# tigerV3s0-2.net
KiCad netlist of a schematic drawn in EAGLE
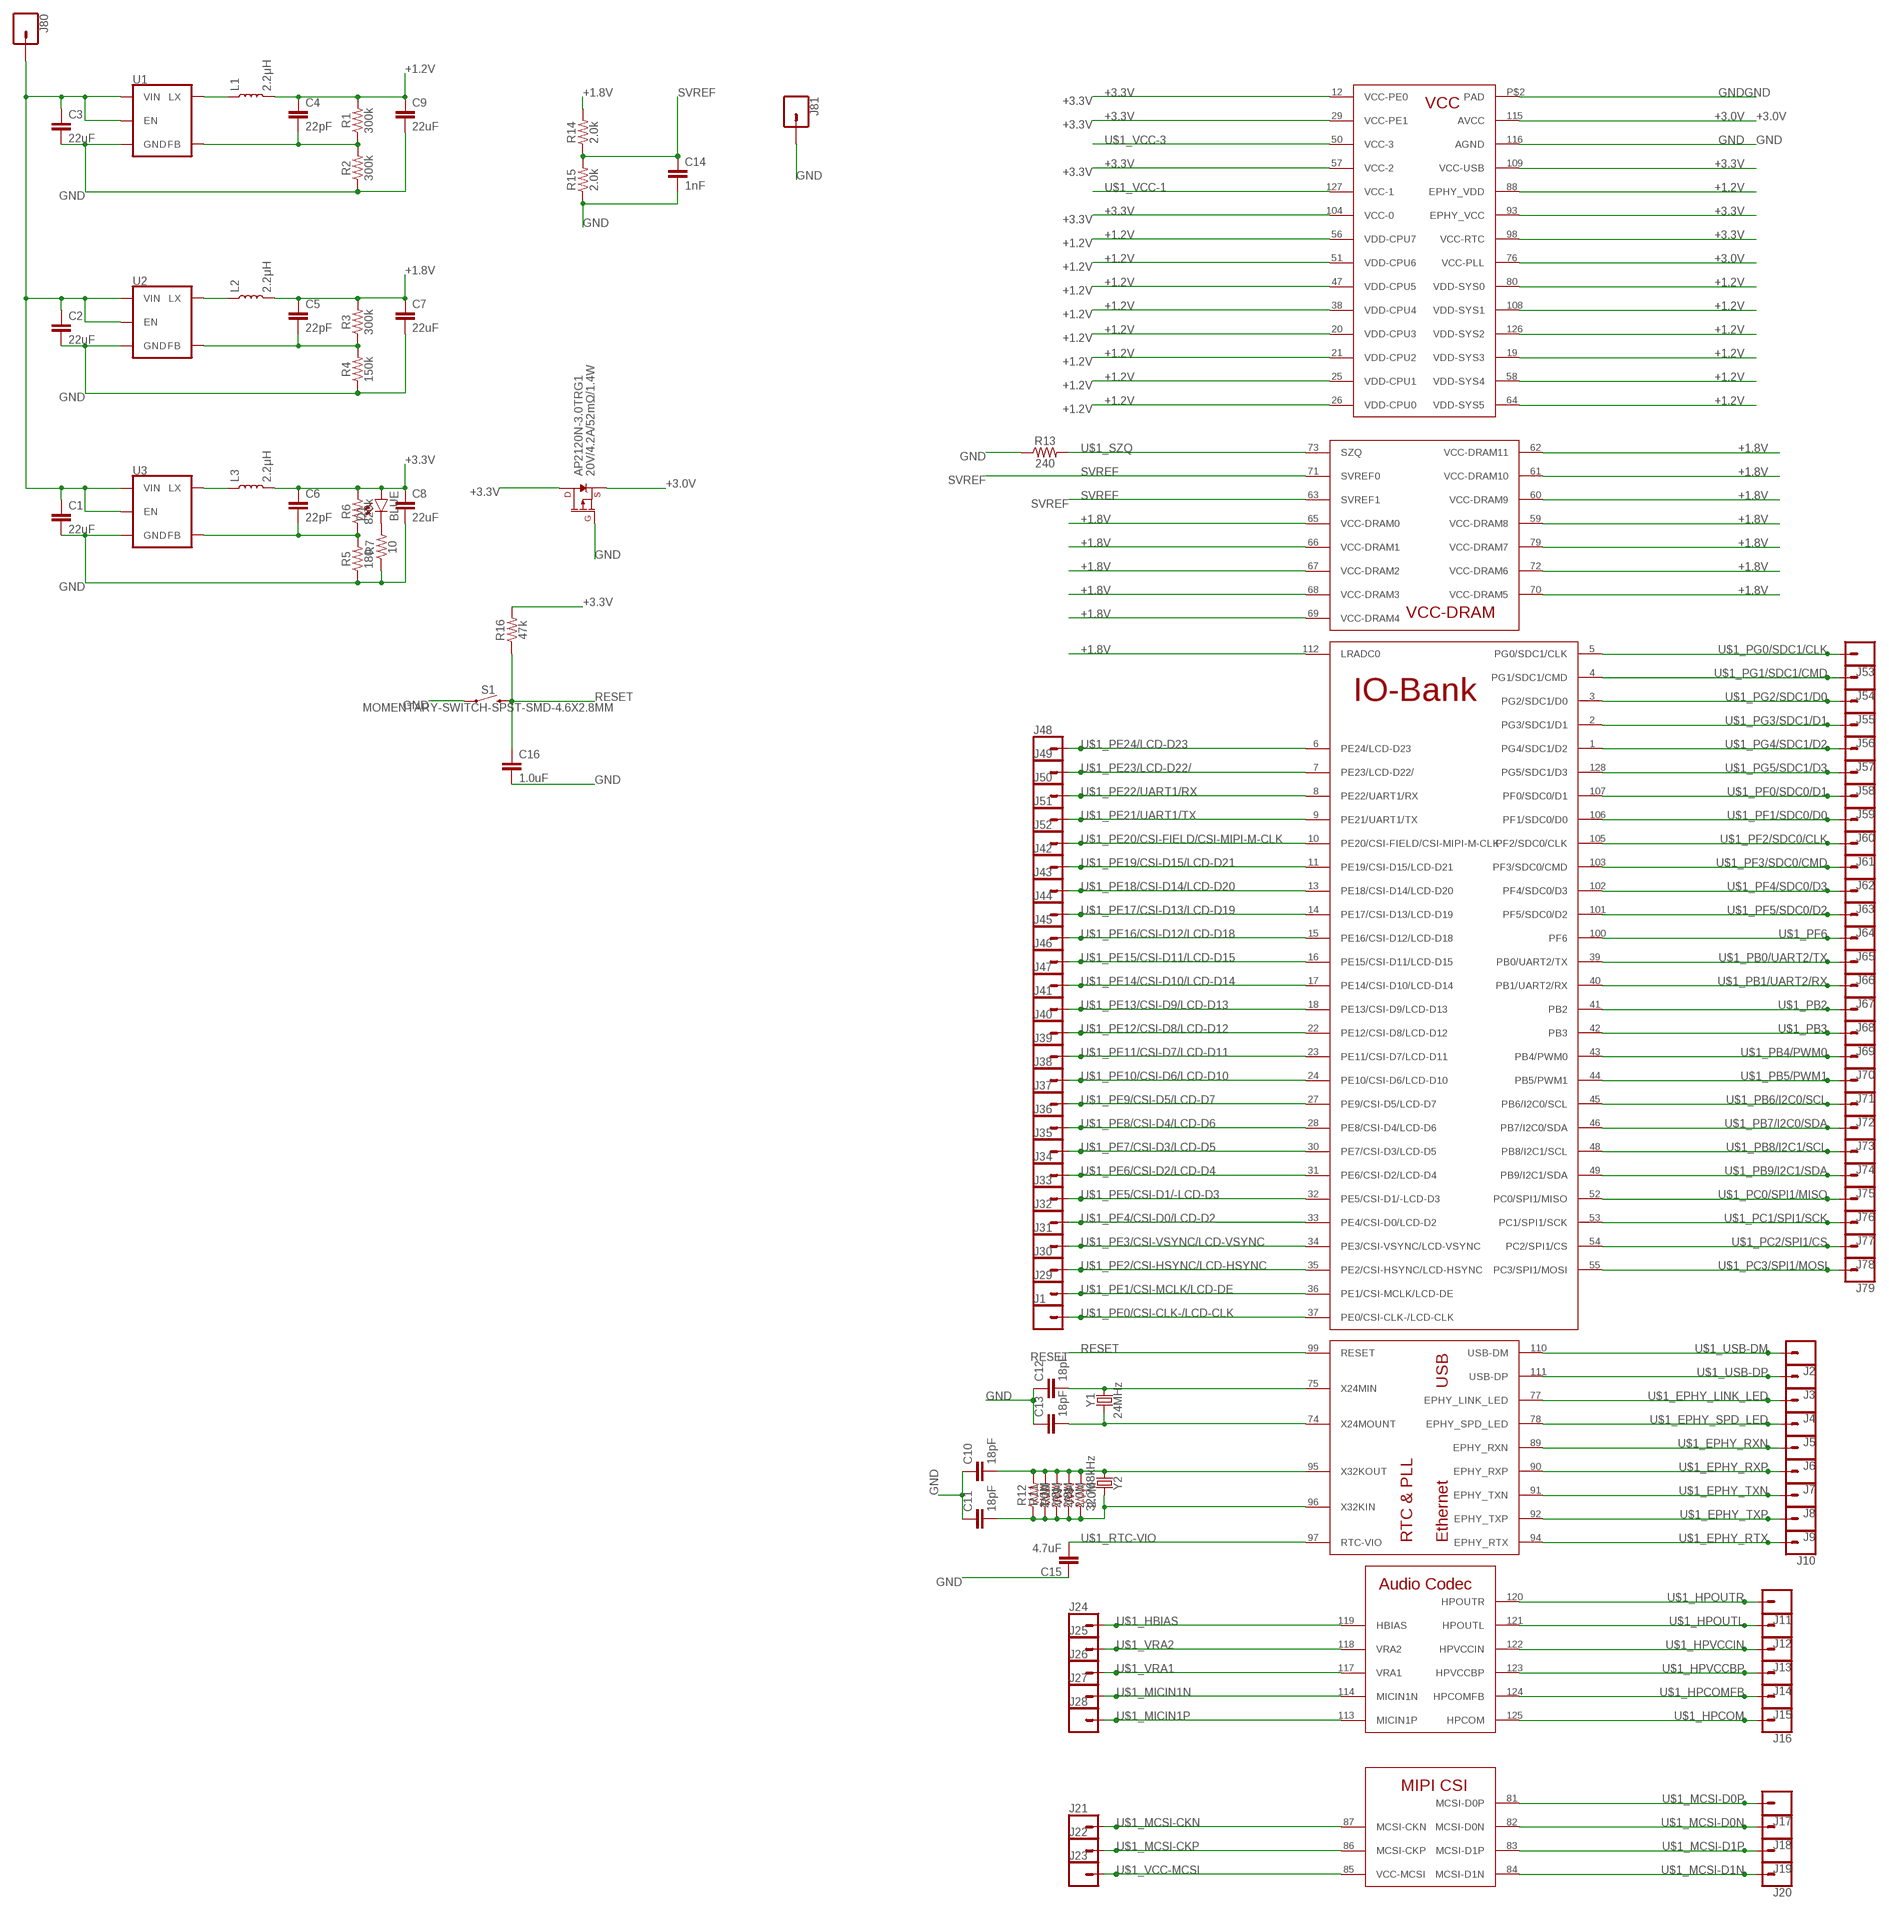
[diagram p0: schematic, sheet 1]

(export (version "E")
  (design (tool "Eeschema 10.0.6"))
  (components
    (comp (ref "AP2120N-3.0TRG1")
      (value "20V/4.2A/52mΩ/1.4W")
      (footprint "eagle-import:SOT23-3")
      (libsource (lib "eagle-import") (part "MOSFET_PCH-DMG2305UX-7"))
    )
    (comp (ref "C1")
      (value "22uF")
      (footprint "eagle-import:0805")
      (libsource (lib "eagle-import") (part "22UF-0805-6.3V-20%"))
    )
    (comp (ref "C2")
      (value "22uF")
      (footprint "eagle-import:0805")
      (libsource (lib "eagle-import") (part "22UF-0805-6.3V-20%"))
    )
    (comp (ref "C3")
      (value "22uF")
      (footprint "eagle-import:0805")
      (libsource (lib "eagle-import") (part "22UF-0805-6.3V-20%"))
    )
    (comp (ref "C4")
      (value "22pF")
      (footprint "eagle-import:0603")
      (libsource (lib "eagle-import") (part "22PF-0603-50V-5%"))
    )
    (comp (ref "C5")
      (value "22pF")
      (footprint "eagle-import:0603")
      (libsource (lib "eagle-import") (part "22PF-0603-50V-5%"))
    )
    (comp (ref "C6")
      (value "22pF")
      (footprint "eagle-import:0603")
      (libsource (lib "eagle-import") (part "22PF-0603-50V-5%"))
    )
    (comp (ref "C7")
      (value "22uF")
      (footprint "eagle-import:0805")
      (libsource (lib "eagle-import") (part "22UF-0805-6.3V-20%"))
    )
    (comp (ref "C8")
      (value "22uF")
      (footprint "eagle-import:0805")
      (libsource (lib "eagle-import") (part "22UF-0805-6.3V-20%"))
    )
    (comp (ref "C9")
      (value "22uF")
      (footprint "eagle-import:0805")
      (libsource (lib "eagle-import") (part "22UF-0805-6.3V-20%"))
    )
    (comp (ref "C10")
      (value "18pF")
      (footprint "eagle-import:0603")
      (libsource (lib "eagle-import") (part "18PF-0603-50V-5%"))
    )
    (comp (ref "C11")
      (value "18pF")
      (footprint "eagle-import:0603")
      (libsource (lib "eagle-import") (part "18PF-0603-50V-5%"))
    )
    (comp (ref "C12")
      (value "18pF")
      (footprint "eagle-import:0603")
      (libsource (lib "eagle-import") (part "18PF-0603-50V-5%"))
    )
    (comp (ref "C13")
      (value "18pF")
      (footprint "eagle-import:0603")
      (libsource (lib "eagle-import") (part "18PF-0603-50V-5%"))
    )
    (comp (ref "C14")
      (value "1nF")
      (footprint "eagle-import:0603")
      (libsource (lib "eagle-import") (part "1.0NF/1000PF-0603-50V-10%"))
    )
    (comp (ref "C15")
      (value "4.7uF")
      (footprint "eagle-import:0603")
      (libsource (lib "eagle-import") (part "4.7UF-0603-6.3V-(10%)"))
    )
    (comp (ref "C16")
      (value "1.0uF")
      (footprint "eagle-import:0603")
      (libsource (lib "eagle-import") (part "1.0UF-0603-16V-10%"))
    )
    (comp (ref "D1")
      (value "BLUE")
      (footprint "eagle-import:LED-0603")
      (libsource (lib "eagle-import") (part "LED-BLUE0603"))
    )
    (comp (ref "J1")
      (value "CONN_01")
      (footprint "eagle-import:1X01")
      (libsource (lib "eagle-import") (part "CONN_01"))
    )
    (comp (ref "J2")
      (value "CONN_01")
      (footprint "eagle-import:1X01")
      (libsource (lib "eagle-import") (part "CONN_01"))
    )
    (comp (ref "J3")
      (value "CONN_01")
      (footprint "eagle-import:1X01")
      (libsource (lib "eagle-import") (part "CONN_01"))
    )
    (comp (ref "J4")
      (value "CONN_01")
      (footprint "eagle-import:1X01")
      (libsource (lib "eagle-import") (part "CONN_01"))
    )
    (comp (ref "J5")
      (value "CONN_01")
      (footprint "eagle-import:1X01")
      (libsource (lib "eagle-import") (part "CONN_01"))
    )
    (comp (ref "J6")
      (value "CONN_01")
      (footprint "eagle-import:1X01")
      (libsource (lib "eagle-import") (part "CONN_01"))
    )
    (comp (ref "J7")
      (value "CONN_01")
      (footprint "eagle-import:1X01")
      (libsource (lib "eagle-import") (part "CONN_01"))
    )
    (comp (ref "J8")
      (value "CONN_01")
      (footprint "eagle-import:1X01")
      (libsource (lib "eagle-import") (part "CONN_01"))
    )
    (comp (ref "J9")
      (value "CONN_01")
      (footprint "eagle-import:1X01")
      (libsource (lib "eagle-import") (part "CONN_01"))
    )
    (comp (ref "J10")
      (value "CONN_01")
      (footprint "eagle-import:1X01")
      (libsource (lib "eagle-import") (part "CONN_01"))
    )
    (comp (ref "J11")
      (value "CONN_01")
      (footprint "eagle-import:1X01")
      (libsource (lib "eagle-import") (part "CONN_01"))
    )
    (comp (ref "J12")
      (value "CONN_01")
      (footprint "eagle-import:1X01")
      (libsource (lib "eagle-import") (part "CONN_01"))
    )
    (comp (ref "J13")
      (value "CONN_01")
      (footprint "eagle-import:1X01")
      (libsource (lib "eagle-import") (part "CONN_01"))
    )
    (comp (ref "J14")
      (value "CONN_01")
      (footprint "eagle-import:1X01")
      (libsource (lib "eagle-import") (part "CONN_01"))
    )
    (comp (ref "J15")
      (value "CONN_01")
      (footprint "eagle-import:1X01")
      (libsource (lib "eagle-import") (part "CONN_01"))
    )
    (comp (ref "J16")
      (value "CONN_01")
      (footprint "eagle-import:1X01")
      (libsource (lib "eagle-import") (part "CONN_01"))
    )
    (comp (ref "J17")
      (value "CONN_01")
      (footprint "eagle-import:1X01")
      (libsource (lib "eagle-import") (part "CONN_01"))
    )
    (comp (ref "J18")
      (value "CONN_01")
      (footprint "eagle-import:1X01")
      (libsource (lib "eagle-import") (part "CONN_01"))
    )
    (comp (ref "J19")
      (value "CONN_01")
      (footprint "eagle-import:1X01")
      (libsource (lib "eagle-import") (part "CONN_01"))
    )
    (comp (ref "J20")
      (value "CONN_01")
      (footprint "eagle-import:1X01")
      (libsource (lib "eagle-import") (part "CONN_01"))
    )
    (comp (ref "J21")
      (value "CONN_01")
      (footprint "eagle-import:1X01")
      (libsource (lib "eagle-import") (part "CONN_01"))
    )
    (comp (ref "J22")
      (value "CONN_01")
      (footprint "eagle-import:1X01")
      (libsource (lib "eagle-import") (part "CONN_01"))
    )
    (comp (ref "J23")
      (value "CONN_01")
      (footprint "eagle-import:1X01")
      (libsource (lib "eagle-import") (part "CONN_01"))
    )
    (comp (ref "J24")
      (value "CONN_01")
      (footprint "eagle-import:1X01")
      (libsource (lib "eagle-import") (part "CONN_01"))
    )
    (comp (ref "J25")
      (value "CONN_01")
      (footprint "eagle-import:1X01")
      (libsource (lib "eagle-import") (part "CONN_01"))
    )
    (comp (ref "J26")
      (value "CONN_01")
      (footprint "eagle-import:1X01")
      (libsource (lib "eagle-import") (part "CONN_01"))
    )
    (comp (ref "J27")
      (value "CONN_01")
      (footprint "eagle-import:1X01")
      (libsource (lib "eagle-import") (part "CONN_01"))
    )
    (comp (ref "J28")
      (value "CONN_01")
      (footprint "eagle-import:1X01")
      (libsource (lib "eagle-import") (part "CONN_01"))
    )
    (comp (ref "J29")
      (value "CONN_01")
      (footprint "eagle-import:1X01")
      (libsource (lib "eagle-import") (part "CONN_01"))
    )
    (comp (ref "J30")
      (value "CONN_01")
      (footprint "eagle-import:1X01")
      (libsource (lib "eagle-import") (part "CONN_01"))
    )
    (comp (ref "J31")
      (value "CONN_01")
      (footprint "eagle-import:1X01")
      (libsource (lib "eagle-import") (part "CONN_01"))
    )
    (comp (ref "J32")
      (value "CONN_01")
      (footprint "eagle-import:1X01")
      (libsource (lib "eagle-import") (part "CONN_01"))
    )
    (comp (ref "J33")
      (value "CONN_01")
      (footprint "eagle-import:1X01")
      (libsource (lib "eagle-import") (part "CONN_01"))
    )
    (comp (ref "J34")
      (value "CONN_01")
      (footprint "eagle-import:1X01")
      (libsource (lib "eagle-import") (part "CONN_01"))
    )
    (comp (ref "J35")
      (value "CONN_01")
      (footprint "eagle-import:1X01")
      (libsource (lib "eagle-import") (part "CONN_01"))
    )
    (comp (ref "J36")
      (value "CONN_01")
      (footprint "eagle-import:1X01")
      (libsource (lib "eagle-import") (part "CONN_01"))
    )
    (comp (ref "J37")
      (value "CONN_01")
      (footprint "eagle-import:1X01")
      (libsource (lib "eagle-import") (part "CONN_01"))
    )
    (comp (ref "J38")
      (value "CONN_01")
      (footprint "eagle-import:1X01")
      (libsource (lib "eagle-import") (part "CONN_01"))
    )
    (comp (ref "J39")
      (value "CONN_01")
      (footprint "eagle-import:1X01")
      (libsource (lib "eagle-import") (part "CONN_01"))
    )
    (comp (ref "J40")
      (value "CONN_01")
      (footprint "eagle-import:1X01")
      (libsource (lib "eagle-import") (part "CONN_01"))
    )
    (comp (ref "J41")
      (value "CONN_01")
      (footprint "eagle-import:1X01")
      (libsource (lib "eagle-import") (part "CONN_01"))
    )
    (comp (ref "J42")
      (value "CONN_01")
      (footprint "eagle-import:1X01")
      (libsource (lib "eagle-import") (part "CONN_01"))
    )
    (comp (ref "J43")
      (value "CONN_01")
      (footprint "eagle-import:1X01")
      (libsource (lib "eagle-import") (part "CONN_01"))
    )
    (comp (ref "J44")
      (value "CONN_01")
      (footprint "eagle-import:1X01")
      (libsource (lib "eagle-import") (part "CONN_01"))
    )
    (comp (ref "J45")
      (value "CONN_01")
      (footprint "eagle-import:1X01")
      (libsource (lib "eagle-import") (part "CONN_01"))
    )
    (comp (ref "J46")
      (value "CONN_01")
      (footprint "eagle-import:1X01")
      (libsource (lib "eagle-import") (part "CONN_01"))
    )
    (comp (ref "J47")
      (value "CONN_01")
      (footprint "eagle-import:1X01")
      (libsource (lib "eagle-import") (part "CONN_01"))
    )
    (comp (ref "J48")
      (value "CONN_01")
      (footprint "eagle-import:1X01")
      (libsource (lib "eagle-import") (part "CONN_01"))
    )
    (comp (ref "J49")
      (value "CONN_01")
      (footprint "eagle-import:1X01")
      (libsource (lib "eagle-import") (part "CONN_01"))
    )
    (comp (ref "J50")
      (value "CONN_01")
      (footprint "eagle-import:1X01")
      (libsource (lib "eagle-import") (part "CONN_01"))
    )
    (comp (ref "J51")
      (value "CONN_01")
      (footprint "eagle-import:1X01")
      (libsource (lib "eagle-import") (part "CONN_01"))
    )
    (comp (ref "J52")
      (value "CONN_01")
      (footprint "eagle-import:1X01")
      (libsource (lib "eagle-import") (part "CONN_01"))
    )
    (comp (ref "J53")
      (value "CONN_01")
      (footprint "eagle-import:1X01")
      (libsource (lib "eagle-import") (part "CONN_01"))
    )
    (comp (ref "J54")
      (value "CONN_01")
      (footprint "eagle-import:1X01")
      (libsource (lib "eagle-import") (part "CONN_01"))
    )
    (comp (ref "J55")
      (value "CONN_01")
      (footprint "eagle-import:1X01")
      (libsource (lib "eagle-import") (part "CONN_01"))
    )
    (comp (ref "J56")
      (value "CONN_01")
      (footprint "eagle-import:1X01")
      (libsource (lib "eagle-import") (part "CONN_01"))
    )
    (comp (ref "J57")
      (value "CONN_01")
      (footprint "eagle-import:1X01")
      (libsource (lib "eagle-import") (part "CONN_01"))
    )
    (comp (ref "J58")
      (value "CONN_01")
      (footprint "eagle-import:1X01")
      (libsource (lib "eagle-import") (part "CONN_01"))
    )
    (comp (ref "J59")
      (value "CONN_01")
      (footprint "eagle-import:1X01")
      (libsource (lib "eagle-import") (part "CONN_01"))
    )
    (comp (ref "J60")
      (value "CONN_01")
      (footprint "eagle-import:1X01")
      (libsource (lib "eagle-import") (part "CONN_01"))
    )
    (comp (ref "J61")
      (value "CONN_01")
      (footprint "eagle-import:1X01")
      (libsource (lib "eagle-import") (part "CONN_01"))
    )
    (comp (ref "J62")
      (value "CONN_01")
      (footprint "eagle-import:1X01")
      (libsource (lib "eagle-import") (part "CONN_01"))
    )
    (comp (ref "J63")
      (value "CONN_01")
      (footprint "eagle-import:1X01")
      (libsource (lib "eagle-import") (part "CONN_01"))
    )
    (comp (ref "J64")
      (value "CONN_01")
      (footprint "eagle-import:1X01")
      (libsource (lib "eagle-import") (part "CONN_01"))
    )
    (comp (ref "J65")
      (value "CONN_01")
      (footprint "eagle-import:1X01")
      (libsource (lib "eagle-import") (part "CONN_01"))
    )
    (comp (ref "J66")
      (value "CONN_01")
      (footprint "eagle-import:1X01")
      (libsource (lib "eagle-import") (part "CONN_01"))
    )
    (comp (ref "J67")
      (value "CONN_01")
      (footprint "eagle-import:1X01")
      (libsource (lib "eagle-import") (part "CONN_01"))
    )
    (comp (ref "J68")
      (value "CONN_01")
      (footprint "eagle-import:1X01")
      (libsource (lib "eagle-import") (part "CONN_01"))
    )
    (comp (ref "J69")
      (value "CONN_01")
      (footprint "eagle-import:1X01")
      (libsource (lib "eagle-import") (part "CONN_01"))
    )
    (comp (ref "J70")
      (value "CONN_01")
      (footprint "eagle-import:1X01")
      (libsource (lib "eagle-import") (part "CONN_01"))
    )
    (comp (ref "J71")
      (value "CONN_01")
      (footprint "eagle-import:1X01")
      (libsource (lib "eagle-import") (part "CONN_01"))
    )
    (comp (ref "J72")
      (value "CONN_01")
      (footprint "eagle-import:1X01")
      (libsource (lib "eagle-import") (part "CONN_01"))
    )
    (comp (ref "J73")
      (value "CONN_01")
      (footprint "eagle-import:1X01")
      (libsource (lib "eagle-import") (part "CONN_01"))
    )
    (comp (ref "J74")
      (value "CONN_01")
      (footprint "eagle-import:1X01")
      (libsource (lib "eagle-import") (part "CONN_01"))
    )
    (comp (ref "J75")
      (value "CONN_01")
      (footprint "eagle-import:1X01")
      (libsource (lib "eagle-import") (part "CONN_01"))
    )
    (comp (ref "J76")
      (value "CONN_01")
      (footprint "eagle-import:1X01")
      (libsource (lib "eagle-import") (part "CONN_01"))
    )
    (comp (ref "J77")
      (value "CONN_01")
      (footprint "eagle-import:1X01")
      (libsource (lib "eagle-import") (part "CONN_01"))
    )
    (comp (ref "J78")
      (value "CONN_01")
      (footprint "eagle-import:1X01")
      (libsource (lib "eagle-import") (part "CONN_01"))
    )
    (comp (ref "J79")
      (value "CONN_01")
      (footprint "eagle-import:1X01")
      (libsource (lib "eagle-import") (part "CONN_01"))
    )
    (comp (ref "J80")
      (value "CONN_01")
      (footprint "eagle-import:1X01")
      (libsource (lib "eagle-import") (part "CONN_01"))
    )
    (comp (ref "J81")
      (value "CONN_01")
      (footprint "eagle-import:1X01")
      (libsource (lib "eagle-import") (part "CONN_01"))
    )
    (comp (ref "L1")
      (value "2.2μH")
      (footprint "eagle-import:0805-WIDE")
      (libsource (lib "eagle-import") (part "2.2μH-0805_WIDE-2.2μH-1.7A-0.14OHM"))
    )
    (comp (ref "L2")
      (value "2.2μH")
      (footprint "eagle-import:0805-WIDE")
      (libsource (lib "eagle-import") (part "2.2μH-0805_WIDE-2.2μH-1.7A-0.14OHM"))
    )
    (comp (ref "L3")
      (value "2.2μH")
      (footprint "eagle-import:0805-WIDE")
      (libsource (lib "eagle-import") (part "2.2μH-0805_WIDE-2.2μH-1.7A-0.14OHM"))
    )
    (comp (ref "R1")
      (value "300k")
      (footprint "eagle-import:0603")
      (libsource (lib "eagle-import") (part "300KOHM-0603-1/10W-1%"))
    )
    (comp (ref "R2")
      (value "300k")
      (footprint "eagle-import:0603")
      (libsource (lib "eagle-import") (part "300KOHM-0603-1/10W-1%"))
    )
    (comp (ref "R3")
      (value "300k")
      (footprint "eagle-import:0603")
      (libsource (lib "eagle-import") (part "300KOHM-0603-1/10W-1%"))
    )
    (comp (ref "R4")
      (value "150k")
      (footprint "eagle-import:0603")
      (libsource (lib "eagle-import") (part "150KOHM-0603-1/10W-1%"))
    )
    (comp (ref "R5")
      (value "180")
      (footprint "eagle-import:0603")
      (libsource (lib "eagle-import") (part "180OHM-0603-1/10W-1%"))
    )
    (comp (ref "R6")
      (value "820k")
      (footprint "eagle-import:0603")
      (libsource (lib "eagle-import") (part "820KOHM-0603-1/10W-1%"))
    )
    (comp (ref "R7")
      (value "10")
      (footprint "eagle-import:0603")
      (libsource (lib "eagle-import") (part "10OHM-0603-1/10W-1%"))
    )
    (comp (ref "R8")
      (value "2.0M")
      (footprint "eagle-import:0603")
      (libsource (lib "eagle-import") (part "2MOHMS-0603-1/10W-1%"))
    )
    (comp (ref "R9")
      (value "2.0M")
      (footprint "eagle-import:0603")
      (libsource (lib "eagle-import") (part "2MOHMS-0603-1/10W-1%"))
    )
    (comp (ref "R10")
      (value "2.0M")
      (footprint "eagle-import:0603")
      (libsource (lib "eagle-import") (part "2MOHMS-0603-1/10W-1%"))
    )
    (comp (ref "R11")
      (value "2.0M")
      (footprint "eagle-import:0603")
      (libsource (lib "eagle-import") (part "2MOHMS-0603-1/10W-1%"))
    )
    (comp (ref "R12")
      (value "2.0M")
      (footprint "eagle-import:0603")
      (libsource (lib "eagle-import") (part "2MOHMS-0603-1/10W-1%"))
    )
    (comp (ref "R13")
      (value "240")
      (footprint "eagle-import:0603")
      (libsource (lib "eagle-import") (part "240OHM-0603-1/10W-1%"))
    )
    (comp (ref "R14")
      (value "2.0k")
      (footprint "eagle-import:0603")
      (libsource (lib "eagle-import") (part "2.0KOHM-0603-1/10W-5%"))
    )
    (comp (ref "R15")
      (value "2.0k")
      (footprint "eagle-import:0603")
      (libsource (lib "eagle-import") (part "2.0KOHM-0603-1/10W-5%"))
    )
    (comp (ref "R16")
      (value "47k")
      (footprint "eagle-import:0603")
      (libsource (lib "eagle-import") (part "47KOHM-0603-1/10W-1%"))
    )
    (comp (ref "S1")
      (value "MOMENTARY-SWITCH-SPST-SMD-4.6X2.8MM")
      (footprint "eagle-import:TACTILE_SWITCH_SMD_4.6X2.8MM")
      (libsource (lib "eagle-import") (part "MOMENTARY-SWITCH-SPST-SMD-4.6X2.8MM"))
    )
    (comp (ref "U$1")
      (value "V3S")
      (footprint "eagle-import:QFP-128")
      (libsource (lib "eagle-import") (part "V3S"))
    )
    (comp (ref "U1")
      (value "AP3429/A")
      (footprint "eagle-import:SOT23-5")
      (libsource (lib "eagle-import") (part "AP3429/A"))
    )
    (comp (ref "U2")
      (value "AP3429/A")
      (footprint "eagle-import:SOT23-5")
      (libsource (lib "eagle-import") (part "AP3429/A"))
    )
    (comp (ref "U3")
      (value "AP3429/A")
      (footprint "eagle-import:SOT23-5")
      (libsource (lib "eagle-import") (part "AP3429/A"))
    )
    (comp (ref "Y1")
      (value "24MHz")
      (footprint "eagle-import:CRYSTAL-SMD-5X3.2-4PAD")
      (libsource (lib "eagle-import") (part "CRYSTAL-24MHZ-SMD-5.0X3.2MM"))
    )
    (comp (ref "Y2")
      (value "32.768kHz")
      (footprint "eagle-import:CRYSTAL-SMD-3.2X1.5MM")
      (libsource (lib "eagle-import") (part "CRYSTAL-32.768KHZSMD-3.2X1.5"))
    )
  )
  (nets
    (net (code "1") (name "/+1.2V") (class "Default")
      (node (ref "C4") (pin "1") (pinfunction "1_1") (pintype "passive"))
      (node (ref "C9") (pin "1") (pinfunction "1_1") (pintype "passive"))
      (node (ref "L1") (pin "2") (pinfunction "2_2") (pintype "passive"))
      (node (ref "R1") (pin "2") (pinfunction "2_2") (pintype "passive"))
      (node (ref "U$1") (pin "108") (pinfunction "VDD-SYS1_108") (pintype "bidirectional"))
      (node (ref "U$1") (pin "126") (pinfunction "VDD-SYS2_126") (pintype "bidirectional"))
      (node (ref "U$1") (pin "19") (pinfunction "VDD-SYS3_19") (pintype "bidirectional"))
      (node (ref "U$1") (pin "20") (pinfunction "VDD-CPU3_20") (pintype "bidirectional"))
      (node (ref "U$1") (pin "21") (pinfunction "VDD-CPU2_21") (pintype "bidirectional"))
      (node (ref "U$1") (pin "25") (pinfunction "VDD-CPU1_25") (pintype "bidirectional"))
      (node (ref "U$1") (pin "26") (pinfunction "VDD-CPU0_26") (pintype "bidirectional"))
      (node (ref "U$1") (pin "38") (pinfunction "VDD-CPU4_38") (pintype "bidirectional"))
      (node (ref "U$1") (pin "47") (pinfunction "VDD-CPU5_47") (pintype "bidirectional"))
      (node (ref "U$1") (pin "51") (pinfunction "VDD-CPU6_51") (pintype "bidirectional"))
      (node (ref "U$1") (pin "56") (pinfunction "VDD-CPU7_56") (pintype "bidirectional"))
      (node (ref "U$1") (pin "58") (pinfunction "VDD-SYS4_58") (pintype "bidirectional"))
      (node (ref "U$1") (pin "64") (pinfunction "VDD-SYS5_64") (pintype "bidirectional"))
      (node (ref "U$1") (pin "80") (pinfunction "VDD-SYS0_80") (pintype "bidirectional"))
      (node (ref "U$1") (pin "88") (pinfunction "EPHY_VDD_88") (pintype "bidirectional"))
    )
    (net (code "2") (name "/+1.8V") (class "Default")
      (node (ref "C5") (pin "1") (pinfunction "1_1") (pintype "passive"))
      (node (ref "C7") (pin "1") (pinfunction "1_1") (pintype "passive"))
      (node (ref "L2") (pin "2") (pinfunction "2_2") (pintype "passive"))
      (node (ref "R14") (pin "2") (pinfunction "2_2") (pintype "passive"))
      (node (ref "R3") (pin "2") (pinfunction "2_2") (pintype "passive"))
      (node (ref "U$1") (pin "112") (pinfunction "LRADC0_112") (pintype "bidirectional"))
      (node (ref "U$1") (pin "59") (pinfunction "VCC-DRAM8_59") (pintype "bidirectional"))
      (node (ref "U$1") (pin "60") (pinfunction "VCC-DRAM9_60") (pintype "bidirectional"))
      (node (ref "U$1") (pin "61") (pinfunction "VCC-DRAM10_61") (pintype "bidirectional"))
      (node (ref "U$1") (pin "62") (pinfunction "VCC-DRAM11_62") (pintype "bidirectional"))
      (node (ref "U$1") (pin "65") (pinfunction "VCC-DRAM0_65") (pintype "bidirectional"))
      (node (ref "U$1") (pin "66") (pinfunction "VCC-DRAM1_66") (pintype "bidirectional"))
      (node (ref "U$1") (pin "67") (pinfunction "VCC-DRAM2_67") (pintype "bidirectional"))
      (node (ref "U$1") (pin "68") (pinfunction "VCC-DRAM3_68") (pintype "bidirectional"))
      (node (ref "U$1") (pin "69") (pinfunction "VCC-DRAM4_69") (pintype "bidirectional"))
      (node (ref "U$1") (pin "70") (pinfunction "VCC-DRAM5_70") (pintype "bidirectional"))
      (node (ref "U$1") (pin "72") (pinfunction "VCC-DRAM6_72") (pintype "bidirectional"))
      (node (ref "U$1") (pin "79") (pinfunction "VCC-DRAM7_79") (pintype "bidirectional"))
    )
    (net (code "3") (name "/+3.0V") (class "Default")
      (node (ref "AP2120N-3.0TRG1") (pin "2") (pinfunction "S_2") (pintype "bidirectional"))
      (node (ref "U$1") (pin "115") (pinfunction "AVCC_115") (pintype "bidirectional"))
      (node (ref "U$1") (pin "76") (pinfunction "VCC-PLL_76") (pintype "bidirectional"))
    )
    (net (code "4") (name "/+3.3V") (class "Default")
      (node (ref "AP2120N-3.0TRG1") (pin "3") (pinfunction "D_3") (pintype "bidirectional"))
      (node (ref "C6") (pin "1") (pinfunction "1_1") (pintype "passive"))
      (node (ref "C8") (pin "1") (pinfunction "1_1") (pintype "passive"))
      (node (ref "D1") (pin "A") (pinfunction "A_A") (pintype "passive"))
      (node (ref "L3") (pin "2") (pinfunction "2_2") (pintype "passive"))
      (node (ref "R16") (pin "2") (pinfunction "2_2") (pintype "passive"))
      (node (ref "R6") (pin "2") (pinfunction "2_2") (pintype "passive"))
      (node (ref "U$1") (pin "104") (pinfunction "VCC-0_104") (pintype "bidirectional"))
      (node (ref "U$1") (pin "109") (pinfunction "VCC-USB_109") (pintype "bidirectional"))
      (node (ref "U$1") (pin "12") (pinfunction "VCC-PE0_12") (pintype "bidirectional"))
      (node (ref "U$1") (pin "29") (pinfunction "VCC-PE1_29") (pintype "bidirectional"))
      (node (ref "U$1") (pin "57") (pinfunction "VCC-2_57") (pintype "bidirectional"))
      (node (ref "U$1") (pin "93") (pinfunction "EPHY_VCC_93") (pintype "bidirectional"))
      (node (ref "U$1") (pin "98") (pinfunction "VCC-RTC_98") (pintype "bidirectional"))
    )
    (net (code "5") (name "/GND") (class "Default")
      (node (ref "AP2120N-3.0TRG1") (pin "1") (pinfunction "G_1") (pintype "bidirectional"))
      (node (ref "C1") (pin "2") (pinfunction "2_2") (pintype "passive"))
      (node (ref "C10") (pin "1") (pinfunction "1_1") (pintype "passive"))
      (node (ref "C11") (pin "1") (pinfunction "1_1") (pintype "passive"))
      (node (ref "C12") (pin "1") (pinfunction "1_1") (pintype "passive"))
      (node (ref "C13") (pin "1") (pinfunction "1_1") (pintype "passive"))
      (node (ref "C14") (pin "2") (pinfunction "2_2") (pintype "passive"))
      (node (ref "C15") (pin "1") (pinfunction "1_1") (pintype "passive"))
      (node (ref "C16") (pin "2") (pinfunction "2_2") (pintype "passive"))
      (node (ref "C2") (pin "2") (pinfunction "2_2") (pintype "passive"))
      (node (ref "C3") (pin "2") (pinfunction "2_2") (pintype "passive"))
      (node (ref "C7") (pin "2") (pinfunction "2_2") (pintype "passive"))
      (node (ref "C8") (pin "2") (pinfunction "2_2") (pintype "passive"))
      (node (ref "C9") (pin "2") (pinfunction "2_2") (pintype "passive"))
      (node (ref "J81") (pin "1") (pinfunction "1_1") (pintype "passive"))
      (node (ref "R13") (pin "1") (pinfunction "1_1") (pintype "passive"))
      (node (ref "R15") (pin "1") (pinfunction "1_1") (pintype "passive"))
      (node (ref "R2") (pin "1") (pinfunction "1_1") (pintype "passive"))
      (node (ref "R4") (pin "1") (pinfunction "1_1") (pintype "passive"))
      (node (ref "R5") (pin "1") (pinfunction "1_1") (pintype "passive"))
      (node (ref "R7") (pin "1") (pinfunction "1_1") (pintype "passive"))
      (node (ref "S1") (pin "1") (pinfunction "1_1") (pintype "passive"))
      (node (ref "S1") (pin "2") (pinfunction "1_2") (pintype "passive"))
      (node (ref "U$1") (pin "116") (pinfunction "AGND_116") (pintype "bidirectional"))
      (node (ref "U$1") (pin "P$2") (pinfunction "PAD_P$2") (pintype "bidirectional"))
      (node (ref "U1") (pin "2") (pinfunction "GND_2") (pintype "input"))
      (node (ref "U2") (pin "2") (pinfunction "GND_2") (pintype "input"))
      (node (ref "U3") (pin "2") (pinfunction "GND_2") (pintype "input"))
    )
    (net (code "6") (name "/RESET") (class "Default")
      (node (ref "C16") (pin "1") (pinfunction "1_1") (pintype "passive"))
      (node (ref "R16") (pin "1") (pinfunction "1_1") (pintype "passive"))
      (node (ref "S1") (pin "3") (pinfunction "2_3") (pintype "passive"))
      (node (ref "S1") (pin "4") (pinfunction "2_4") (pintype "passive"))
      (node (ref "U$1") (pin "99") (pinfunction "RESET_99") (pintype "bidirectional"))
    )
    (net (code "7") (name "/SVREF") (class "Default")
      (node (ref "C14") (pin "1") (pinfunction "1_1") (pintype "passive"))
      (node (ref "R14") (pin "1") (pinfunction "1_1") (pintype "passive"))
      (node (ref "R15") (pin "2") (pinfunction "2_2") (pintype "passive"))
      (node (ref "U$1") (pin "63") (pinfunction "SVREF1_63") (pintype "bidirectional"))
      (node (ref "U$1") (pin "71") (pinfunction "SVREF0_71") (pintype "bidirectional"))
    )
    (net (code "8") (name "/U$1_EPHY_LINK_LED") (class "Default")
      (node (ref "J4") (pin "1") (pinfunction "1_1") (pintype "passive"))
      (node (ref "U$1") (pin "77") (pinfunction "EPHY_LINK_LED_77") (pintype "bidirectional"))
    )
    (net (code "9") (name "/U$1_EPHY_RTX") (class "Default")
      (node (ref "J10") (pin "1") (pinfunction "1_1") (pintype "passive"))
      (node (ref "U$1") (pin "94") (pinfunction "EPHY_RTX_94") (pintype "bidirectional"))
    )
    (net (code "10") (name "/U$1_EPHY_RXN") (class "Default")
      (node (ref "J6") (pin "1") (pinfunction "1_1") (pintype "passive"))
      (node (ref "U$1") (pin "89") (pinfunction "EPHY_RXN_89") (pintype "bidirectional"))
    )
    (net (code "11") (name "/U$1_EPHY_RXP") (class "Default")
      (node (ref "J7") (pin "1") (pinfunction "1_1") (pintype "passive"))
      (node (ref "U$1") (pin "90") (pinfunction "EPHY_RXP_90") (pintype "bidirectional"))
    )
    (net (code "12") (name "/U$1_EPHY_SPD_LED") (class "Default")
      (node (ref "J5") (pin "1") (pinfunction "1_1") (pintype "passive"))
      (node (ref "U$1") (pin "78") (pinfunction "EPHY_SPD_LED_78") (pintype "bidirectional"))
    )
    (net (code "13") (name "/U$1_EPHY_TXN") (class "Default")
      (node (ref "J8") (pin "1") (pinfunction "1_1") (pintype "passive"))
      (node (ref "U$1") (pin "91") (pinfunction "EPHY_TXN_91") (pintype "bidirectional"))
    )
    (net (code "14") (name "/U$1_EPHY_TXP") (class "Default")
      (node (ref "J9") (pin "1") (pinfunction "1_1") (pintype "passive"))
      (node (ref "U$1") (pin "92") (pinfunction "EPHY_TXP_92") (pintype "bidirectional"))
    )
    (net (code "15") (name "/U$1_HBIAS") (class "Default")
      (node (ref "J24") (pin "1") (pinfunction "1_1") (pintype "passive"))
      (node (ref "U$1") (pin "119") (pinfunction "HBIAS_119") (pintype "bidirectional"))
    )
    (net (code "16") (name "/U$1_HPCOM") (class "Default")
      (node (ref "J16") (pin "1") (pinfunction "1_1") (pintype "passive"))
      (node (ref "U$1") (pin "125") (pinfunction "HPCOM_125") (pintype "bidirectional"))
    )
    (net (code "17") (name "/U$1_HPCOMFB") (class "Default")
      (node (ref "J15") (pin "1") (pinfunction "1_1") (pintype "passive"))
      (node (ref "U$1") (pin "124") (pinfunction "HPCOMFB_124") (pintype "bidirectional"))
    )
    (net (code "18") (name "/U$1_HPOUTL") (class "Default")
      (node (ref "J12") (pin "1") (pinfunction "1_1") (pintype "passive"))
      (node (ref "U$1") (pin "121") (pinfunction "HPOUTL_121") (pintype "bidirectional"))
    )
    (net (code "19") (name "/U$1_HPOUTR") (class "Default")
      (node (ref "J11") (pin "1") (pinfunction "1_1") (pintype "passive"))
      (node (ref "U$1") (pin "120") (pinfunction "HPOUTR_120") (pintype "bidirectional"))
    )
    (net (code "20") (name "/U$1_HPVCCBP") (class "Default")
      (node (ref "J14") (pin "1") (pinfunction "1_1") (pintype "passive"))
      (node (ref "U$1") (pin "123") (pinfunction "HPVCCBP_123") (pintype "bidirectional"))
    )
    (net (code "21") (name "/U$1_HPVCCIN") (class "Default")
      (node (ref "J13") (pin "1") (pinfunction "1_1") (pintype "passive"))
      (node (ref "U$1") (pin "122") (pinfunction "HPVCCIN_122") (pintype "bidirectional"))
    )
    (net (code "22") (name "/U$1_MCSI-CKN") (class "Default")
      (node (ref "J21") (pin "1") (pinfunction "1_1") (pintype "passive"))
      (node (ref "U$1") (pin "87") (pinfunction "MCSI-CKN_87") (pintype "bidirectional"))
    )
    (net (code "23") (name "/U$1_MCSI-CKP") (class "Default")
      (node (ref "J22") (pin "1") (pinfunction "1_1") (pintype "passive"))
      (node (ref "U$1") (pin "86") (pinfunction "MCSI-CKP_86") (pintype "bidirectional"))
    )
    (net (code "24") (name "/U$1_MCSI-D0N") (class "Default")
      (node (ref "J18") (pin "1") (pinfunction "1_1") (pintype "passive"))
      (node (ref "U$1") (pin "82") (pinfunction "MCSI-D0N_82") (pintype "bidirectional"))
    )
    (net (code "25") (name "/U$1_MCSI-D0P") (class "Default")
      (node (ref "J17") (pin "1") (pinfunction "1_1") (pintype "passive"))
      (node (ref "U$1") (pin "81") (pinfunction "MCSI-D0P_81") (pintype "bidirectional"))
    )
    (net (code "26") (name "/U$1_MCSI-D1N") (class "Default")
      (node (ref "J20") (pin "1") (pinfunction "1_1") (pintype "passive"))
      (node (ref "U$1") (pin "84") (pinfunction "MCSI-D1N_84") (pintype "bidirectional"))
    )
    (net (code "27") (name "/U$1_MCSI-D1P") (class "Default")
      (node (ref "J19") (pin "1") (pinfunction "1_1") (pintype "passive"))
      (node (ref "U$1") (pin "83") (pinfunction "MCSI-D1P_83") (pintype "bidirectional"))
    )
    (net (code "28") (name "/U$1_MICIN1N") (class "Default")
      (node (ref "J27") (pin "1") (pinfunction "1_1") (pintype "passive"))
      (node (ref "U$1") (pin "114") (pinfunction "MICIN1N_114") (pintype "bidirectional"))
    )
    (net (code "29") (name "/U$1_MICIN1P") (class "Default")
      (node (ref "J28") (pin "1") (pinfunction "1_1") (pintype "passive"))
      (node (ref "U$1") (pin "113") (pinfunction "MICIN1P_113") (pintype "bidirectional"))
    )
    (net (code "30") (name "/U$1_PB0{slash}UART2{slash}TX") (class "Default")
      (node (ref "J66") (pin "1") (pinfunction "1_1") (pintype "passive"))
      (node (ref "U$1") (pin "39") (pinfunction "PB0/UART2/TX_39") (pintype "bidirectional"))
    )
    (net (code "31") (name "/U$1_PB1{slash}UART2{slash}RX") (class "Default")
      (node (ref "J67") (pin "1") (pinfunction "1_1") (pintype "passive"))
      (node (ref "U$1") (pin "40") (pinfunction "PB1/UART2/RX_40") (pintype "bidirectional"))
    )
    (net (code "32") (name "/U$1_PB2") (class "Default")
      (node (ref "J68") (pin "1") (pinfunction "1_1") (pintype "passive"))
      (node (ref "U$1") (pin "41") (pinfunction "PB2_41") (pintype "bidirectional"))
    )
    (net (code "33") (name "/U$1_PB3") (class "Default")
      (node (ref "J69") (pin "1") (pinfunction "1_1") (pintype "passive"))
      (node (ref "U$1") (pin "42") (pinfunction "PB3_42") (pintype "bidirectional"))
    )
    (net (code "34") (name "/U$1_PB4{slash}PWM0") (class "Default")
      (node (ref "J70") (pin "1") (pinfunction "1_1") (pintype "passive"))
      (node (ref "U$1") (pin "43") (pinfunction "PB4/PWM0_43") (pintype "bidirectional"))
    )
    (net (code "35") (name "/U$1_PB5{slash}PWM1") (class "Default")
      (node (ref "J71") (pin "1") (pinfunction "1_1") (pintype "passive"))
      (node (ref "U$1") (pin "44") (pinfunction "PB5/PWM1_44") (pintype "bidirectional"))
    )
    (net (code "36") (name "/U$1_PB6{slash}I2C0{slash}SCL") (class "Default")
      (node (ref "J72") (pin "1") (pinfunction "1_1") (pintype "passive"))
      (node (ref "U$1") (pin "45") (pinfunction "PB6/I2C0/SCL_45") (pintype "bidirectional"))
    )
    (net (code "37") (name "/U$1_PB7{slash}I2C0{slash}SDA") (class "Default")
      (node (ref "J73") (pin "1") (pinfunction "1_1") (pintype "passive"))
      (node (ref "U$1") (pin "46") (pinfunction "PB7/I2C0/SDA_46") (pintype "bidirectional"))
    )
    (net (code "38") (name "/U$1_PB8{slash}I2C1{slash}SCL") (class "Default")
      (node (ref "J74") (pin "1") (pinfunction "1_1") (pintype "passive"))
      (node (ref "U$1") (pin "48") (pinfunction "PB8/I2C1/SCL_48") (pintype "bidirectional"))
    )
    (net (code "39") (name "/U$1_PB9{slash}I2C1{slash}SDA") (class "Default")
      (node (ref "J75") (pin "1") (pinfunction "1_1") (pintype "passive"))
      (node (ref "U$1") (pin "49") (pinfunction "PB9/I2C1/SDA_49") (pintype "bidirectional"))
    )
    (net (code "40") (name "/U$1_PC0{slash}SPI1{slash}MISO") (class "Default")
      (node (ref "J76") (pin "1") (pinfunction "1_1") (pintype "passive"))
      (node (ref "U$1") (pin "52") (pinfunction "PC0/SPI1/MISO_52") (pintype "bidirectional"))
    )
    (net (code "41") (name "/U$1_PC1{slash}SPI1{slash}SCK") (class "Default")
      (node (ref "J77") (pin "1") (pinfunction "1_1") (pintype "passive"))
      (node (ref "U$1") (pin "53") (pinfunction "PC1/SPI1/SCK_53") (pintype "bidirectional"))
    )
    (net (code "42") (name "/U$1_PC2{slash}SPI1{slash}CS") (class "Default")
      (node (ref "J78") (pin "1") (pinfunction "1_1") (pintype "passive"))
      (node (ref "U$1") (pin "54") (pinfunction "PC2/SPI1/CS_54") (pintype "bidirectional"))
    )
    (net (code "43") (name "/U$1_PC3{slash}SPI1{slash}MOSI") (class "Default")
      (node (ref "J79") (pin "1") (pinfunction "1_1") (pintype "passive"))
      (node (ref "U$1") (pin "55") (pinfunction "PC3/SPI1/MOSI_55") (pintype "bidirectional"))
    )
    (net (code "44") (name "/U$1_PE0{slash}CSI-CLK-{slash}LCD-CLK") (class "Default")
      (node (ref "J1") (pin "1") (pinfunction "1_1") (pintype "passive"))
      (node (ref "U$1") (pin "37") (pinfunction "PE0/CSI-CLK-/LCD-CLK_37") (pintype "bidirectional"))
    )
    (net (code "45") (name "/U$1_PE1{slash}CSI-MCLK{slash}LCD-DE") (class "Default")
      (node (ref "J29") (pin "1") (pinfunction "1_1") (pintype "passive"))
      (node (ref "U$1") (pin "36") (pinfunction "PE1/CSI-MCLK/LCD-DE_36") (pintype "bidirectional"))
    )
    (net (code "46") (name "/U$1_PE2{slash}CSI-HSYNC{slash}LCD-HSYNC") (class "Default")
      (node (ref "J30") (pin "1") (pinfunction "1_1") (pintype "passive"))
      (node (ref "U$1") (pin "35") (pinfunction "PE2/CSI-HSYNC/LCD-HSYNC_35") (pintype "bidirectional"))
    )
    (net (code "47") (name "/U$1_PE3{slash}CSI-VSYNC{slash}LCD-VSYNC") (class "Default")
      (node (ref "J31") (pin "1") (pinfunction "1_1") (pintype "passive"))
      (node (ref "U$1") (pin "34") (pinfunction "PE3/CSI-VSYNC/LCD-VSYNC_34") (pintype "bidirectional"))
    )
    (net (code "48") (name "/U$1_PE4{slash}CSI-D0{slash}LCD-D2") (class "Default")
      (node (ref "J32") (pin "1") (pinfunction "1_1") (pintype "passive"))
      (node (ref "U$1") (pin "33") (pinfunction "PE4/CSI-D0/LCD-D2_33") (pintype "bidirectional"))
    )
    (net (code "49") (name "/U$1_PE5{slash}CSI-D1{slash}-LCD-D3") (class "Default")
      (node (ref "J33") (pin "1") (pinfunction "1_1") (pintype "passive"))
      (node (ref "U$1") (pin "32") (pinfunction "PE5/CSI-D1/-LCD-D3_32") (pintype "bidirectional"))
    )
    (net (code "50") (name "/U$1_PE6{slash}CSI-D2{slash}LCD-D4") (class "Default")
      (node (ref "J34") (pin "1") (pinfunction "1_1") (pintype "passive"))
      (node (ref "U$1") (pin "31") (pinfunction "PE6/CSI-D2/LCD-D4_31") (pintype "bidirectional"))
    )
    (net (code "51") (name "/U$1_PE7{slash}CSI-D3{slash}LCD-D5") (class "Default")
      (node (ref "J35") (pin "1") (pinfunction "1_1") (pintype "passive"))
      (node (ref "U$1") (pin "30") (pinfunction "PE7/CSI-D3/LCD-D5_30") (pintype "bidirectional"))
    )
    (net (code "52") (name "/U$1_PE8{slash}CSI-D4{slash}LCD-D6") (class "Default")
      (node (ref "J36") (pin "1") (pinfunction "1_1") (pintype "passive"))
      (node (ref "U$1") (pin "28") (pinfunction "PE8/CSI-D4/LCD-D6_28") (pintype "bidirectional"))
    )
    (net (code "53") (name "/U$1_PE9{slash}CSI-D5{slash}LCD-D7") (class "Default")
      (node (ref "J37") (pin "1") (pinfunction "1_1") (pintype "passive"))
      (node (ref "U$1") (pin "27") (pinfunction "PE9/CSI-D5/LCD-D7_27") (pintype "bidirectional"))
    )
    (net (code "54") (name "/U$1_PE10{slash}CSI-D6{slash}LCD-D10") (class "Default")
      (node (ref "J38") (pin "1") (pinfunction "1_1") (pintype "passive"))
      (node (ref "U$1") (pin "24") (pinfunction "PE10/CSI-D6/LCD-D10_24") (pintype "bidirectional"))
    )
    (net (code "55") (name "/U$1_PE11{slash}CSI-D7{slash}LCD-D11") (class "Default")
      (node (ref "J39") (pin "1") (pinfunction "1_1") (pintype "passive"))
      (node (ref "U$1") (pin "23") (pinfunction "PE11/CSI-D7/LCD-D11_23") (pintype "bidirectional"))
    )
    (net (code "56") (name "/U$1_PE12{slash}CSI-D8{slash}LCD-D12") (class "Default")
      (node (ref "J40") (pin "1") (pinfunction "1_1") (pintype "passive"))
      (node (ref "U$1") (pin "22") (pinfunction "PE12/CSI-D8/LCD-D12_22") (pintype "bidirectional"))
    )
    (net (code "57") (name "/U$1_PE13{slash}CSI-D9{slash}LCD-D13") (class "Default")
      (node (ref "J41") (pin "1") (pinfunction "1_1") (pintype "passive"))
      (node (ref "U$1") (pin "18") (pinfunction "PE13/CSI-D9/LCD-D13_18") (pintype "bidirectional"))
    )
    (net (code "58") (name "/U$1_PE14{slash}CSI-D10{slash}LCD-D14") (class "Default")
      (node (ref "J47") (pin "1") (pinfunction "1_1") (pintype "passive"))
      (node (ref "U$1") (pin "17") (pinfunction "PE14/CSI-D10/LCD-D14_17") (pintype "bidirectional"))
    )
    (net (code "59") (name "/U$1_PE15{slash}CSI-D11{slash}LCD-D15") (class "Default")
      (node (ref "J46") (pin "1") (pinfunction "1_1") (pintype "passive"))
      (node (ref "U$1") (pin "16") (pinfunction "PE15/CSI-D11/LCD-D15_16") (pintype "bidirectional"))
    )
    (net (code "60") (name "/U$1_PE16{slash}CSI-D12{slash}LCD-D18") (class "Default")
      (node (ref "J45") (pin "1") (pinfunction "1_1") (pintype "passive"))
      (node (ref "U$1") (pin "15") (pinfunction "PE16/CSI-D12/LCD-D18_15") (pintype "bidirectional"))
    )
    (net (code "61") (name "/U$1_PE17{slash}CSI-D13{slash}LCD-D19") (class "Default")
      (node (ref "J44") (pin "1") (pinfunction "1_1") (pintype "passive"))
      (node (ref "U$1") (pin "14") (pinfunction "PE17/CSI-D13/LCD-D19_14") (pintype "bidirectional"))
    )
    (net (code "62") (name "/U$1_PE18{slash}CSI-D14{slash}LCD-D20") (class "Default")
      (node (ref "J43") (pin "1") (pinfunction "1_1") (pintype "passive"))
      (node (ref "U$1") (pin "13") (pinfunction "PE18/CSI-D14/LCD-D20_13") (pintype "bidirectional"))
    )
    (net (code "63") (name "/U$1_PE19{slash}CSI-D15{slash}LCD-D21") (class "Default")
      (node (ref "J42") (pin "1") (pinfunction "1_1") (pintype "passive"))
      (node (ref "U$1") (pin "11") (pinfunction "PE19/CSI-D15/LCD-D21_11") (pintype "bidirectional"))
    )
    (net (code "64") (name "/U$1_PE20{slash}CSI-FIELD{slash}CSI-MIPI-M-CLK") (class "Default")
      (node (ref "J52") (pin "1") (pinfunction "1_1") (pintype "passive"))
      (node (ref "U$1") (pin "10") (pinfunction "PE20/CSI-FIELD/CSI-MIPI-M-CLK_10") (pintype "bidirectional"))
    )
    (net (code "65") (name "/U$1_PE21{slash}UART1{slash}TX") (class "Default")
      (node (ref "J51") (pin "1") (pinfunction "1_1") (pintype "passive"))
      (node (ref "U$1") (pin "9") (pinfunction "PE21/UART1/TX_9") (pintype "bidirectional"))
    )
    (net (code "66") (name "/U$1_PE22{slash}UART1{slash}RX") (class "Default")
      (node (ref "J50") (pin "1") (pinfunction "1_1") (pintype "passive"))
      (node (ref "U$1") (pin "8") (pinfunction "PE22/UART1/RX_8") (pintype "bidirectional"))
    )
    (net (code "67") (name "/U$1_PE23{slash}LCD-D22{slash}") (class "Default")
      (node (ref "J49") (pin "1") (pinfunction "1_1") (pintype "passive"))
      (node (ref "U$1") (pin "7") (pinfunction "PE23/LCD-D22/_7") (pintype "bidirectional"))
    )
    (net (code "68") (name "/U$1_PE24{slash}LCD-D23") (class "Default")
      (node (ref "J48") (pin "1") (pinfunction "1_1") (pintype "passive"))
      (node (ref "U$1") (pin "6") (pinfunction "PE24/LCD-D23_6") (pintype "bidirectional"))
    )
    (net (code "69") (name "/U$1_PF0{slash}SDC0{slash}D1") (class "Default")
      (node (ref "J59") (pin "1") (pinfunction "1_1") (pintype "passive"))
      (node (ref "U$1") (pin "107") (pinfunction "PF0/SDC0/D1_107") (pintype "bidirectional"))
    )
    (net (code "70") (name "/U$1_PF1{slash}SDC0{slash}D0") (class "Default")
      (node (ref "J60") (pin "1") (pinfunction "1_1") (pintype "passive"))
      (node (ref "U$1") (pin "106") (pinfunction "PF1/SDC0/D0_106") (pintype "bidirectional"))
    )
    (net (code "71") (name "/U$1_PF2{slash}SDC0{slash}CLK") (class "Default")
      (node (ref "J61") (pin "1") (pinfunction "1_1") (pintype "passive"))
      (node (ref "U$1") (pin "105") (pinfunction "PF2/SDC0/CLK_105") (pintype "bidirectional"))
    )
    (net (code "72") (name "/U$1_PF3{slash}SDC0{slash}CMD") (class "Default")
      (node (ref "J62") (pin "1") (pinfunction "1_1") (pintype "passive"))
      (node (ref "U$1") (pin "103") (pinfunction "PF3/SDC0/CMD_103") (pintype "bidirectional"))
    )
    (net (code "73") (name "/U$1_PF4{slash}SDC0{slash}D3") (class "Default")
      (node (ref "J63") (pin "1") (pinfunction "1_1") (pintype "passive"))
      (node (ref "U$1") (pin "102") (pinfunction "PF4/SDC0/D3_102") (pintype "bidirectional"))
    )
    (net (code "74") (name "/U$1_PF5{slash}SDC0{slash}D2") (class "Default")
      (node (ref "J64") (pin "1") (pinfunction "1_1") (pintype "passive"))
      (node (ref "U$1") (pin "101") (pinfunction "PF5/SDC0/D2_101") (pintype "bidirectional"))
    )
    (net (code "75") (name "/U$1_PF6") (class "Default")
      (node (ref "J65") (pin "1") (pinfunction "1_1") (pintype "passive"))
      (node (ref "U$1") (pin "100") (pinfunction "PF6_100") (pintype "bidirectional"))
    )
    (net (code "76") (name "/U$1_PG0{slash}SDC1{slash}CLK") (class "Default")
      (node (ref "J53") (pin "1") (pinfunction "1_1") (pintype "passive"))
      (node (ref "U$1") (pin "5") (pinfunction "PG0/SDC1/CLK_5") (pintype "bidirectional"))
    )
    (net (code "77") (name "/U$1_PG1{slash}SDC1{slash}CMD") (class "Default")
      (node (ref "J54") (pin "1") (pinfunction "1_1") (pintype "passive"))
      (node (ref "U$1") (pin "4") (pinfunction "PG1/SDC1/CMD_4") (pintype "bidirectional"))
    )
    (net (code "78") (name "/U$1_PG2{slash}SDC1{slash}D0") (class "Default")
      (node (ref "J55") (pin "1") (pinfunction "1_1") (pintype "passive"))
      (node (ref "U$1") (pin "3") (pinfunction "PG2/SDC1/D0_3") (pintype "bidirectional"))
    )
    (net (code "79") (name "/U$1_PG3{slash}SDC1{slash}D1") (class "Default")
      (node (ref "J56") (pin "1") (pinfunction "1_1") (pintype "passive"))
      (node (ref "U$1") (pin "2") (pinfunction "PG3/SDC1/D1_2") (pintype "bidirectional"))
    )
    (net (code "80") (name "/U$1_PG4{slash}SDC1{slash}D2") (class "Default")
      (node (ref "J57") (pin "1") (pinfunction "1_1") (pintype "passive"))
      (node (ref "U$1") (pin "1") (pinfunction "PG4/SDC1/D2_1") (pintype "bidirectional"))
    )
    (net (code "81") (name "/U$1_PG5{slash}SDC1{slash}D3") (class "Default")
      (node (ref "J58") (pin "1") (pinfunction "1_1") (pintype "passive"))
      (node (ref "U$1") (pin "128") (pinfunction "PG5/SDC1/D3_128") (pintype "bidirectional"))
    )
    (net (code "82") (name "/U$1_RTC-VIO") (class "Default")
      (node (ref "C15") (pin "2") (pinfunction "2_2") (pintype "passive"))
      (node (ref "U$1") (pin "97") (pinfunction "RTC-VIO_97") (pintype "bidirectional"))
    )
    (net (code "83") (name "/U$1_SZQ") (class "Default")
      (node (ref "R13") (pin "2") (pinfunction "2_2") (pintype "passive"))
      (node (ref "U$1") (pin "73") (pinfunction "SZQ_73") (pintype "bidirectional"))
    )
    (net (code "84") (name "/U$1_USB-DM") (class "Default")
      (node (ref "J2") (pin "1") (pinfunction "1_1") (pintype "passive"))
      (node (ref "U$1") (pin "110") (pinfunction "USB-DM_110") (pintype "bidirectional"))
    )
    (net (code "85") (name "/U$1_USB-DP") (class "Default")
      (node (ref "J3") (pin "1") (pinfunction "1_1") (pintype "passive"))
      (node (ref "U$1") (pin "111") (pinfunction "USB-DP_111") (pintype "bidirectional"))
    )
    (net (code "86") (name "/U$1_VCC-1") (class "Default")
      (node (ref "U$1") (pin "127") (pinfunction "VCC-1_127") (pintype "bidirectional"))
    )
    (net (code "87") (name "/U$1_VCC-3") (class "Default")
      (node (ref "U$1") (pin "50") (pinfunction "VCC-3_50") (pintype "bidirectional"))
    )
    (net (code "88") (name "/U$1_VCC-MCSI") (class "Default")
      (node (ref "J23") (pin "1") (pinfunction "1_1") (pintype "passive"))
      (node (ref "U$1") (pin "85") (pinfunction "VCC-MCSI_85") (pintype "bidirectional"))
    )
    (net (code "89") (name "/U$1_VRA1") (class "Default")
      (node (ref "J26") (pin "1") (pinfunction "1_1") (pintype "passive"))
      (node (ref "U$1") (pin "117") (pinfunction "VRA1_117") (pintype "bidirectional"))
    )
    (net (code "90") (name "/U$1_VRA2") (class "Default")
      (node (ref "J25") (pin "1") (pinfunction "1_1") (pintype "passive"))
      (node (ref "U$1") (pin "118") (pinfunction "VRA2_118") (pintype "bidirectional"))
    )
    (net (code "91") (name "Net-(D1-PadC)") (class "Default")
      (node (ref "D1") (pin "C") (pinfunction "C_C") (pintype "passive"))
      (node (ref "R7") (pin "2") (pinfunction "2_2") (pintype "passive"))
    )
    (net (code "92") (name "Net-(U$1-X24MIN)") (class "Default")
      (node (ref "C12") (pin "2") (pinfunction "2_2") (pintype "passive"))
      (node (ref "U$1") (pin "75") (pinfunction "X24MIN_75") (pintype "bidirectional"))
      (node (ref "Y1") (pin "3") (pinfunction "2_3") (pintype "passive"))
    )
    (net (code "93") (name "Net-(U$1-X24MOUNT)") (class "Default")
      (node (ref "C13") (pin "2") (pinfunction "2_2") (pintype "passive"))
      (node (ref "U$1") (pin "74") (pinfunction "X24MOUNT_74") (pintype "bidirectional"))
      (node (ref "Y1") (pin "1") (pinfunction "1_1") (pintype "passive"))
    )
    (net (code "94") (name "Net-(U$1-X32KIN)") (class "Default")
      (node (ref "C11") (pin "2") (pinfunction "2_2") (pintype "passive"))
      (node (ref "R10") (pin "1") (pinfunction "1_1") (pintype "passive"))
      (node (ref "R11") (pin "1") (pinfunction "1_1") (pintype "passive"))
      (node (ref "R12") (pin "1") (pinfunction "1_1") (pintype "passive"))
      (node (ref "R8") (pin "1") (pinfunction "1_1") (pintype "passive"))
      (node (ref "R9") (pin "1") (pinfunction "1_1") (pintype "passive"))
      (node (ref "U$1") (pin "96") (pinfunction "X32KIN_96") (pintype "bidirectional"))
      (node (ref "Y2") (pin "P$2") (pinfunction "2_P$2") (pintype "passive"))
    )
    (net (code "95") (name "Net-(U$1-X32KOUT)") (class "Default")
      (node (ref "C10") (pin "2") (pinfunction "2_2") (pintype "passive"))
      (node (ref "R10") (pin "2") (pinfunction "2_2") (pintype "passive"))
      (node (ref "R11") (pin "2") (pinfunction "2_2") (pintype "passive"))
      (node (ref "R12") (pin "2") (pinfunction "2_2") (pintype "passive"))
      (node (ref "R8") (pin "2") (pinfunction "2_2") (pintype "passive"))
      (node (ref "R9") (pin "2") (pinfunction "2_2") (pintype "passive"))
      (node (ref "U$1") (pin "95") (pinfunction "X32KOUT_95") (pintype "bidirectional"))
      (node (ref "Y2") (pin "P$1") (pinfunction "1_P$1") (pintype "passive"))
    )
    (net (code "96") (name "Net-(U1-EN)") (class "Default")
      (node (ref "C1") (pin "1") (pinfunction "1_1") (pintype "passive"))
      (node (ref "C2") (pin "1") (pinfunction "1_1") (pintype "passive"))
      (node (ref "C3") (pin "1") (pinfunction "1_1") (pintype "passive"))
      (node (ref "J80") (pin "1") (pinfunction "1_1") (pintype "passive"))
      (node (ref "U1") (pin "1") (pinfunction "EN_1") (pintype "input"))
      (node (ref "U1") (pin "4") (pinfunction "VIN_4") (pintype "input"))
      (node (ref "U2") (pin "1") (pinfunction "EN_1") (pintype "input"))
      (node (ref "U2") (pin "4") (pinfunction "VIN_4") (pintype "input"))
      (node (ref "U3") (pin "1") (pinfunction "EN_1") (pintype "input"))
      (node (ref "U3") (pin "4") (pinfunction "VIN_4") (pintype "input"))
    )
    (net (code "97") (name "Net-(U1-FB)") (class "Default")
      (node (ref "C4") (pin "2") (pinfunction "2_2") (pintype "passive"))
      (node (ref "R1") (pin "1") (pinfunction "1_1") (pintype "passive"))
      (node (ref "R2") (pin "2") (pinfunction "2_2") (pintype "passive"))
      (node (ref "U1") (pin "5") (pinfunction "FB_5") (pintype "passive"))
    )
    (net (code "98") (name "Net-(U1-LX)") (class "Default")
      (node (ref "L1") (pin "1") (pinfunction "1_1") (pintype "passive"))
      (node (ref "U1") (pin "3") (pinfunction "LX_3") (pintype "input"))
    )
    (net (code "99") (name "Net-(U2-FB)") (class "Default")
      (node (ref "C5") (pin "2") (pinfunction "2_2") (pintype "passive"))
      (node (ref "R3") (pin "1") (pinfunction "1_1") (pintype "passive"))
      (node (ref "R4") (pin "2") (pinfunction "2_2") (pintype "passive"))
      (node (ref "U2") (pin "5") (pinfunction "FB_5") (pintype "passive"))
    )
    (net (code "100") (name "Net-(U2-LX)") (class "Default")
      (node (ref "L2") (pin "1") (pinfunction "1_1") (pintype "passive"))
      (node (ref "U2") (pin "3") (pinfunction "LX_3") (pintype "input"))
    )
    (net (code "101") (name "Net-(U3-FB)") (class "Default")
      (node (ref "C6") (pin "2") (pinfunction "2_2") (pintype "passive"))
      (node (ref "R5") (pin "2") (pinfunction "2_2") (pintype "passive"))
      (node (ref "R6") (pin "1") (pinfunction "1_1") (pintype "passive"))
      (node (ref "U3") (pin "5") (pinfunction "FB_5") (pintype "passive"))
    )
    (net (code "102") (name "Net-(U3-LX)") (class "Default")
      (node (ref "L3") (pin "1") (pinfunction "1_1") (pintype "passive"))
      (node (ref "U3") (pin "3") (pinfunction "LX_3") (pintype "input"))
    )
  )
)
